# SDRAM.net
KiCad netlist of a schematic drawn in Altium Designer
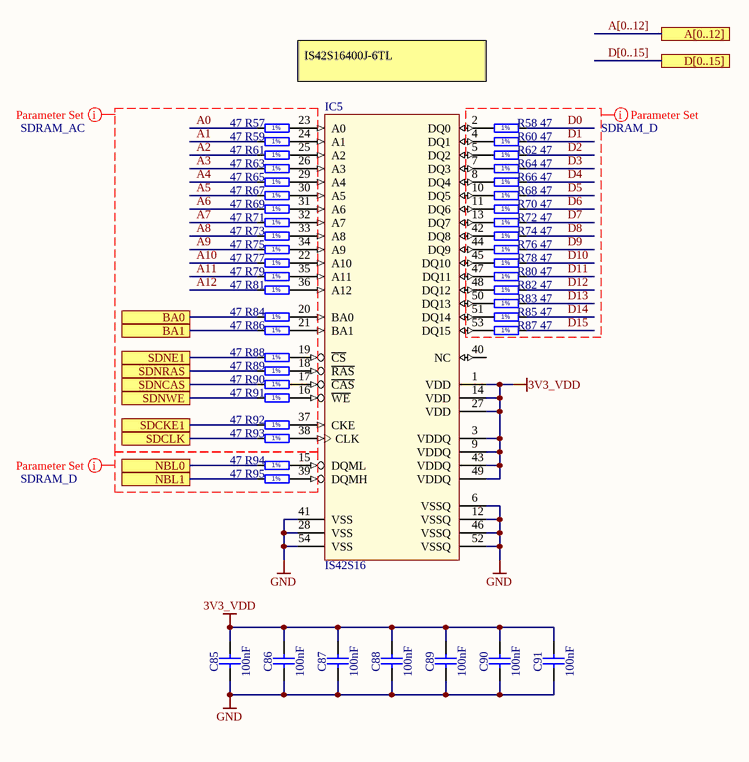
[diagram p0: SDRAM.SchDoc]

(export (version "E")
  (design (tool "Eeschema 10.0.6"))
  (components
    (comp (ref "C85")
      (value "100nF")
      (footprint "CAPC1005X55N")
      (description "Non-polarised capacitor")
      (fields
        (field (name "PART NUMBER") "CC0402_100NF_16V_10%_X5R")
        (field (name "VOLTAGE") "16V")
        (field (name "AUTHOR") "CERN DEM JLC")
      )
      (libsource (lib "Capacitors") (part "Capacitor - non polarized"))
    )
    (comp (ref "C86")
      (value "100nF")
      (footprint "CAPC1005X55N")
      (description "Non-polarised capacitor")
      (fields
        (field (name "PART NUMBER") "CC0402_100NF_16V_10%_X5R")
        (field (name "VOLTAGE") "16V")
        (field (name "AUTHOR") "CERN DEM JLC")
      )
      (libsource (lib "Capacitors") (part "Capacitor - non polarized"))
    )
    (comp (ref "C87")
      (value "100nF")
      (footprint "CAPC1005X55N")
      (description "Non-polarised capacitor")
      (fields
        (field (name "PART NUMBER") "CC0402_100NF_16V_10%_X5R")
        (field (name "VOLTAGE") "16V")
        (field (name "AUTHOR") "CERN DEM JLC")
      )
      (libsource (lib "Capacitors") (part "Capacitor - non polarized"))
    )
    (comp (ref "C88")
      (value "100nF")
      (footprint "CAPC1005X55N")
      (description "Non-polarised capacitor")
      (fields
        (field (name "PART NUMBER") "CC0402_100NF_16V_10%_X5R")
        (field (name "VOLTAGE") "16V")
        (field (name "AUTHOR") "CERN DEM JLC")
      )
      (libsource (lib "Capacitors") (part "Capacitor - non polarized"))
    )
    (comp (ref "C89")
      (value "100nF")
      (footprint "CAPC1005X55N")
      (description "Non-polarised capacitor")
      (fields
        (field (name "PART NUMBER") "CC0402_100NF_16V_10%_X5R")
        (field (name "VOLTAGE") "16V")
        (field (name "AUTHOR") "CERN DEM JLC")
      )
      (libsource (lib "Capacitors") (part "Capacitor - non polarized"))
    )
    (comp (ref "C90")
      (value "100nF")
      (footprint "CAPC1005X55N")
      (description "Non-polarised capacitor")
      (fields
        (field (name "PART NUMBER") "CC0402_100NF_16V_10%_X5R")
        (field (name "VOLTAGE") "16V")
        (field (name "AUTHOR") "CERN DEM JLC")
      )
      (libsource (lib "Capacitors") (part "Capacitor - non polarized"))
    )
    (comp (ref "C91")
      (value "100nF")
      (footprint "CAPC1005X55N")
      (description "Non-polarised capacitor")
      (fields
        (field (name "PART NUMBER") "CC0402_100NF_16V_10%_X5R")
        (field (name "VOLTAGE") "16V")
        (field (name "AUTHOR") "CERN DEM JLC")
      )
      (libsource (lib "Capacitors") (part "Capacitor - non polarized"))
    )
    (comp (ref "IC5")
      (value "IS42S16")
      (footprint "TSOP-54")
      (description "SDRAM 64m 200mhz 54tsop")
      (fields (field (name "MP") "IS42S16400J-5TL-TR") (field (name "MF") "ISSI"))
      (libsource (lib "IS42S16") (part "IS42S16"))
    )
    (comp (ref "R57")
      (value "47")
      (footprint "RESC1005X40N")
      (description "Resistor - 1%")
      (fields
        (field (name "PART NUMBER") "R0402_47R_1%_0.0625W_100PPM")
        (field (name "POWER") "0.0625W")
        (field (name "AUTHOR") "CERN DEM JLC")
      )
      (libsource (lib "Resistors") (part "Resistor - 1%"))
    )
    (comp (ref "R58")
      (value "47")
      (footprint "RESC1005X40N")
      (description "Resistor - 1%")
      (fields
        (field (name "PART NUMBER") "R0402_47R_1%_0.0625W_100PPM")
        (field (name "POWER") "0.0625W")
        (field (name "AUTHOR") "CERN DEM JLC")
      )
      (libsource (lib "Resistors") (part "Resistor - 1%"))
    )
    (comp (ref "R59")
      (value "47")
      (footprint "RESC1005X40N")
      (description "Resistor - 1%")
      (fields
        (field (name "PART NUMBER") "R0402_47R_1%_0.0625W_100PPM")
        (field (name "POWER") "0.0625W")
        (field (name "AUTHOR") "CERN DEM JLC")
      )
      (libsource (lib "Resistors") (part "Resistor - 1%"))
    )
    (comp (ref "R60")
      (value "47")
      (footprint "RESC1005X40N")
      (description "Resistor - 1%")
      (fields
        (field (name "PART NUMBER") "R0402_47R_1%_0.0625W_100PPM")
        (field (name "POWER") "0.0625W")
        (field (name "AUTHOR") "CERN DEM JLC")
      )
      (libsource (lib "Resistors") (part "Resistor - 1%"))
    )
    (comp (ref "R61")
      (value "47")
      (footprint "RESC1005X40N")
      (description "Resistor - 1%")
      (fields
        (field (name "PART NUMBER") "R0402_47R_1%_0.0625W_100PPM")
        (field (name "POWER") "0.0625W")
        (field (name "AUTHOR") "CERN DEM JLC")
      )
      (libsource (lib "Resistors") (part "Resistor - 1%"))
    )
    (comp (ref "R62")
      (value "47")
      (footprint "RESC1005X40N")
      (description "Resistor - 1%")
      (fields
        (field (name "PART NUMBER") "R0402_47R_1%_0.0625W_100PPM")
        (field (name "POWER") "0.0625W")
        (field (name "AUTHOR") "CERN DEM JLC")
      )
      (libsource (lib "Resistors") (part "Resistor - 1%"))
    )
    (comp (ref "R63")
      (value "47")
      (footprint "RESC1005X40N")
      (description "Resistor - 1%")
      (fields
        (field (name "PART NUMBER") "R0402_47R_1%_0.0625W_100PPM")
        (field (name "POWER") "0.0625W")
        (field (name "AUTHOR") "CERN DEM JLC")
      )
      (libsource (lib "Resistors") (part "Resistor - 1%"))
    )
    (comp (ref "R64")
      (value "47")
      (footprint "RESC1005X40N")
      (description "Resistor - 1%")
      (fields
        (field (name "PART NUMBER") "R0402_47R_1%_0.0625W_100PPM")
        (field (name "POWER") "0.0625W")
        (field (name "AUTHOR") "CERN DEM JLC")
      )
      (libsource (lib "Resistors") (part "Resistor - 1%"))
    )
    (comp (ref "R65")
      (value "47")
      (footprint "RESC1005X40N")
      (description "Resistor - 1%")
      (fields
        (field (name "PART NUMBER") "R0402_47R_1%_0.0625W_100PPM")
        (field (name "POWER") "0.0625W")
        (field (name "AUTHOR") "CERN DEM JLC")
      )
      (libsource (lib "Resistors") (part "Resistor - 1%"))
    )
    (comp (ref "R66")
      (value "47")
      (footprint "RESC1005X40N")
      (description "Resistor - 1%")
      (fields
        (field (name "PART NUMBER") "R0402_47R_1%_0.0625W_100PPM")
        (field (name "POWER") "0.0625W")
        (field (name "AUTHOR") "CERN DEM JLC")
      )
      (libsource (lib "Resistors") (part "Resistor - 1%"))
    )
    (comp (ref "R67")
      (value "47")
      (footprint "RESC1005X40N")
      (description "Resistor - 1%")
      (fields
        (field (name "PART NUMBER") "R0402_47R_1%_0.0625W_100PPM")
        (field (name "POWER") "0.0625W")
        (field (name "AUTHOR") "CERN DEM JLC")
      )
      (libsource (lib "Resistors") (part "Resistor - 1%"))
    )
    (comp (ref "R68")
      (value "47")
      (footprint "RESC1005X40N")
      (description "Resistor - 1%")
      (fields
        (field (name "PART NUMBER") "R0402_47R_1%_0.0625W_100PPM")
        (field (name "POWER") "0.0625W")
        (field (name "AUTHOR") "CERN DEM JLC")
      )
      (libsource (lib "Resistors") (part "Resistor - 1%"))
    )
    (comp (ref "R69")
      (value "47")
      (footprint "RESC1005X40N")
      (description "Resistor - 1%")
      (fields
        (field (name "PART NUMBER") "R0402_47R_1%_0.0625W_100PPM")
        (field (name "POWER") "0.0625W")
        (field (name "AUTHOR") "CERN DEM JLC")
      )
      (libsource (lib "Resistors") (part "Resistor - 1%"))
    )
    (comp (ref "R70")
      (value "47")
      (footprint "RESC1005X40N")
      (description "Resistor - 1%")
      (fields
        (field (name "PART NUMBER") "R0402_47R_1%_0.0625W_100PPM")
        (field (name "POWER") "0.0625W")
        (field (name "AUTHOR") "CERN DEM JLC")
      )
      (libsource (lib "Resistors") (part "Resistor - 1%"))
    )
    (comp (ref "R71")
      (value "47")
      (footprint "RESC1005X40N")
      (description "Resistor - 1%")
      (fields
        (field (name "PART NUMBER") "R0402_47R_1%_0.0625W_100PPM")
        (field (name "POWER") "0.0625W")
        (field (name "AUTHOR") "CERN DEM JLC")
      )
      (libsource (lib "Resistors") (part "Resistor - 1%"))
    )
    (comp (ref "R72")
      (value "47")
      (footprint "RESC1005X40N")
      (description "Resistor - 1%")
      (fields
        (field (name "PART NUMBER") "R0402_47R_1%_0.0625W_100PPM")
        (field (name "POWER") "0.0625W")
        (field (name "AUTHOR") "CERN DEM JLC")
      )
      (libsource (lib "Resistors") (part "Resistor - 1%"))
    )
    (comp (ref "R73")
      (value "47")
      (footprint "RESC1005X40N")
      (description "Resistor - 1%")
      (fields
        (field (name "PART NUMBER") "R0402_47R_1%_0.0625W_100PPM")
        (field (name "POWER") "0.0625W")
        (field (name "AUTHOR") "CERN DEM JLC")
      )
      (libsource (lib "Resistors") (part "Resistor - 1%"))
    )
    (comp (ref "R74")
      (value "47")
      (footprint "RESC1005X40N")
      (description "Resistor - 1%")
      (fields
        (field (name "PART NUMBER") "R0402_47R_1%_0.0625W_100PPM")
        (field (name "POWER") "0.0625W")
        (field (name "AUTHOR") "CERN DEM JLC")
      )
      (libsource (lib "Resistors") (part "Resistor - 1%"))
    )
    (comp (ref "R75")
      (value "47")
      (footprint "RESC1005X40N")
      (description "Resistor - 1%")
      (fields
        (field (name "PART NUMBER") "R0402_47R_1%_0.0625W_100PPM")
        (field (name "POWER") "0.0625W")
        (field (name "AUTHOR") "CERN DEM JLC")
      )
      (libsource (lib "Resistors") (part "Resistor - 1%"))
    )
    (comp (ref "R76")
      (value "47")
      (footprint "RESC1005X40N")
      (description "Resistor - 1%")
      (fields
        (field (name "PART NUMBER") "R0402_47R_1%_0.0625W_100PPM")
        (field (name "POWER") "0.0625W")
        (field (name "AUTHOR") "CERN DEM JLC")
      )
      (libsource (lib "Resistors") (part "Resistor - 1%"))
    )
    (comp (ref "R77")
      (value "47")
      (footprint "RESC1005X40N")
      (description "Resistor - 1%")
      (fields
        (field (name "PART NUMBER") "R0402_47R_1%_0.0625W_100PPM")
        (field (name "POWER") "0.0625W")
        (field (name "AUTHOR") "CERN DEM JLC")
      )
      (libsource (lib "Resistors") (part "Resistor - 1%"))
    )
    (comp (ref "R78")
      (value "47")
      (footprint "RESC1005X40N")
      (description "Resistor - 1%")
      (fields
        (field (name "PART NUMBER") "R0402_47R_1%_0.0625W_100PPM")
        (field (name "POWER") "0.0625W")
        (field (name "AUTHOR") "CERN DEM JLC")
      )
      (libsource (lib "Resistors") (part "Resistor - 1%"))
    )
    (comp (ref "R79")
      (value "47")
      (footprint "RESC1005X40N")
      (description "Resistor - 1%")
      (fields
        (field (name "PART NUMBER") "R0402_47R_1%_0.0625W_100PPM")
        (field (name "POWER") "0.0625W")
        (field (name "AUTHOR") "CERN DEM JLC")
      )
      (libsource (lib "Resistors") (part "Resistor - 1%"))
    )
    (comp (ref "R80")
      (value "47")
      (footprint "RESC1005X40N")
      (description "Resistor - 1%")
      (fields
        (field (name "PART NUMBER") "R0402_47R_1%_0.0625W_100PPM")
        (field (name "POWER") "0.0625W")
        (field (name "AUTHOR") "CERN DEM JLC")
      )
      (libsource (lib "Resistors") (part "Resistor - 1%"))
    )
    (comp (ref "R81")
      (value "47")
      (footprint "RESC1005X40N")
      (description "Resistor - 1%")
      (fields
        (field (name "PART NUMBER") "R0402_47R_1%_0.0625W_100PPM")
        (field (name "POWER") "0.0625W")
        (field (name "AUTHOR") "CERN DEM JLC")
      )
      (libsource (lib "Resistors") (part "Resistor - 1%"))
    )
    (comp (ref "R82")
      (value "47")
      (footprint "RESC1005X40N")
      (description "Resistor - 1%")
      (fields
        (field (name "PART NUMBER") "R0402_47R_1%_0.0625W_100PPM")
        (field (name "POWER") "0.0625W")
        (field (name "AUTHOR") "CERN DEM JLC")
      )
      (libsource (lib "Resistors") (part "Resistor - 1%"))
    )
    (comp (ref "R83")
      (value "47")
      (footprint "RESC1005X40N")
      (description "Resistor - 1%")
      (fields
        (field (name "PART NUMBER") "R0402_47R_1%_0.0625W_100PPM")
        (field (name "POWER") "0.0625W")
        (field (name "AUTHOR") "CERN DEM JLC")
      )
      (libsource (lib "Resistors") (part "Resistor - 1%"))
    )
    (comp (ref "R84")
      (value "47")
      (footprint "RESC1005X40N")
      (description "Resistor - 1%")
      (fields
        (field (name "PART NUMBER") "R0402_47R_1%_0.0625W_100PPM")
        (field (name "POWER") "0.0625W")
        (field (name "AUTHOR") "CERN DEM JLC")
      )
      (libsource (lib "Resistors") (part "Resistor - 1%"))
    )
    (comp (ref "R85")
      (value "47")
      (footprint "RESC1005X40N")
      (description "Resistor - 1%")
      (fields
        (field (name "PART NUMBER") "R0402_47R_1%_0.0625W_100PPM")
        (field (name "POWER") "0.0625W")
        (field (name "AUTHOR") "CERN DEM JLC")
      )
      (libsource (lib "Resistors") (part "Resistor - 1%"))
    )
    (comp (ref "R86")
      (value "47")
      (footprint "RESC1005X40N")
      (description "Resistor - 1%")
      (fields
        (field (name "PART NUMBER") "R0402_47R_1%_0.0625W_100PPM")
        (field (name "POWER") "0.0625W")
        (field (name "AUTHOR") "CERN DEM JLC")
      )
      (libsource (lib "Resistors") (part "Resistor - 1%"))
    )
    (comp (ref "R87")
      (value "47")
      (footprint "RESC1005X40N")
      (description "Resistor - 1%")
      (fields
        (field (name "PART NUMBER") "R0402_47R_1%_0.0625W_100PPM")
        (field (name "POWER") "0.0625W")
        (field (name "AUTHOR") "CERN DEM JLC")
      )
      (libsource (lib "Resistors") (part "Resistor - 1%"))
    )
    (comp (ref "R88")
      (value "47")
      (footprint "RESC1005X40N")
      (description "Resistor - 1%")
      (fields
        (field (name "PART NUMBER") "R0402_47R_1%_0.0625W_100PPM")
        (field (name "POWER") "0.0625W")
        (field (name "AUTHOR") "CERN DEM JLC")
      )
      (libsource (lib "Resistors") (part "Resistor - 1%"))
    )
    (comp (ref "R89")
      (value "47")
      (footprint "RESC1005X40N")
      (description "Resistor - 1%")
      (fields
        (field (name "PART NUMBER") "R0402_47R_1%_0.0625W_100PPM")
        (field (name "POWER") "0.0625W")
        (field (name "AUTHOR") "CERN DEM JLC")
      )
      (libsource (lib "Resistors") (part "Resistor - 1%"))
    )
    (comp (ref "R90")
      (value "47")
      (footprint "RESC1005X40N")
      (description "Resistor - 1%")
      (fields
        (field (name "PART NUMBER") "R0402_47R_1%_0.0625W_100PPM")
        (field (name "POWER") "0.0625W")
        (field (name "AUTHOR") "CERN DEM JLC")
      )
      (libsource (lib "Resistors") (part "Resistor - 1%"))
    )
    (comp (ref "R91")
      (value "47")
      (footprint "RESC1005X40N")
      (description "Resistor - 1%")
      (fields
        (field (name "PART NUMBER") "R0402_47R_1%_0.0625W_100PPM")
        (field (name "POWER") "0.0625W")
        (field (name "AUTHOR") "CERN DEM JLC")
      )
      (libsource (lib "Resistors") (part "Resistor - 1%"))
    )
    (comp (ref "R92")
      (value "47")
      (footprint "RESC1005X40N")
      (description "Resistor - 1%")
      (fields
        (field (name "PART NUMBER") "R0402_47R_1%_0.0625W_100PPM")
        (field (name "POWER") "0.0625W")
        (field (name "AUTHOR") "CERN DEM JLC")
      )
      (libsource (lib "Resistors") (part "Resistor - 1%"))
    )
    (comp (ref "R93")
      (value "47")
      (footprint "RESC1005X40N")
      (description "Resistor - 1%")
      (fields
        (field (name "PART NUMBER") "R0402_47R_1%_0.0625W_100PPM")
        (field (name "POWER") "0.0625W")
        (field (name "AUTHOR") "CERN DEM JLC")
      )
      (libsource (lib "Resistors") (part "Resistor - 1%"))
    )
    (comp (ref "R94")
      (value "47")
      (footprint "RESC1005X40N")
      (description "Resistor - 1%")
      (fields
        (field (name "PART NUMBER") "R0402_47R_1%_0.0625W_100PPM")
        (field (name "POWER") "0.0625W")
        (field (name "AUTHOR") "CERN DEM JLC")
      )
      (libsource (lib "Resistors") (part "Resistor - 1%"))
    )
    (comp (ref "R95")
      (value "47")
      (footprint "RESC1005X40N")
      (description "Resistor - 1%")
      (fields
        (field (name "PART NUMBER") "R0402_47R_1%_0.0625W_100PPM")
        (field (name "POWER") "0.0625W")
        (field (name "AUTHOR") "CERN DEM JLC")
      )
      (libsource (lib "Resistors") (part "Resistor - 1%"))
    )
  )
  (nets
    (net (code "1") (name "/A0") (class "Default")
      (node (ref "R57") (pin "2") (pinfunction "2_2") (pintype "passive"))
    )
    (net (code "2") (name "/A1") (class "Default")
      (node (ref "R59") (pin "2") (pinfunction "2_2") (pintype "passive"))
    )
    (net (code "3") (name "/A2") (class "Default")
      (node (ref "R61") (pin "2") (pinfunction "2_2") (pintype "passive"))
    )
    (net (code "4") (name "/A3") (class "Default")
      (node (ref "R63") (pin "2") (pinfunction "2_2") (pintype "passive"))
    )
    (net (code "5") (name "/A4") (class "Default")
      (node (ref "R65") (pin "2") (pinfunction "2_2") (pintype "passive"))
    )
    (net (code "6") (name "/A5") (class "Default")
      (node (ref "R67") (pin "2") (pinfunction "2_2") (pintype "passive"))
    )
    (net (code "7") (name "/A6") (class "Default")
      (node (ref "R69") (pin "2") (pinfunction "2_2") (pintype "passive"))
    )
    (net (code "8") (name "/A7") (class "Default")
      (node (ref "R71") (pin "2") (pinfunction "2_2") (pintype "passive"))
    )
    (net (code "9") (name "/A8") (class "Default")
      (node (ref "R73") (pin "2") (pinfunction "2_2") (pintype "passive"))
    )
    (net (code "10") (name "/A9") (class "Default")
      (node (ref "R75") (pin "2") (pinfunction "2_2") (pintype "passive"))
    )
    (net (code "11") (name "/A10") (class "Default")
      (node (ref "R77") (pin "2") (pinfunction "2_2") (pintype "passive"))
    )
    (net (code "12") (name "/A11") (class "Default")
      (node (ref "R79") (pin "2") (pinfunction "2_2") (pintype "passive"))
    )
    (net (code "13") (name "/A12") (class "Default")
      (node (ref "R81") (pin "2") (pinfunction "2_2") (pintype "passive"))
    )
    (net (code "15") (name "/BA0") (class "Default")
      (node (ref "R84") (pin "2") (pinfunction "2_2") (pintype "passive"))
    )
    (net (code "16") (name "/BA1") (class "Default")
      (node (ref "R86") (pin "2") (pinfunction "2_2") (pintype "passive"))
    )
    (net (code "17") (name "/D0") (class "Default")
      (node (ref "R58") (pin "2") (pinfunction "2_2") (pintype "passive"))
    )
    (net (code "18") (name "/D1") (class "Default")
      (node (ref "R60") (pin "2") (pinfunction "2_2") (pintype "passive"))
    )
    (net (code "19") (name "/D2") (class "Default")
      (node (ref "R62") (pin "2") (pinfunction "2_2") (pintype "passive"))
    )
    (net (code "20") (name "/D3") (class "Default")
      (node (ref "R64") (pin "2") (pinfunction "2_2") (pintype "passive"))
    )
    (net (code "21") (name "/D4") (class "Default")
      (node (ref "R66") (pin "2") (pinfunction "2_2") (pintype "passive"))
    )
    (net (code "22") (name "/D5") (class "Default")
      (node (ref "R68") (pin "2") (pinfunction "2_2") (pintype "passive"))
    )
    (net (code "23") (name "/D6") (class "Default")
      (node (ref "R70") (pin "2") (pinfunction "2_2") (pintype "passive"))
    )
    (net (code "24") (name "/D7") (class "Default")
      (node (ref "R72") (pin "2") (pinfunction "2_2") (pintype "passive"))
    )
    (net (code "25") (name "/D8") (class "Default")
      (node (ref "R74") (pin "2") (pinfunction "2_2") (pintype "passive"))
    )
    (net (code "26") (name "/D9") (class "Default")
      (node (ref "R76") (pin "2") (pinfunction "2_2") (pintype "passive"))
    )
    (net (code "27") (name "/D10") (class "Default")
      (node (ref "R78") (pin "2") (pinfunction "2_2") (pintype "passive"))
    )
    (net (code "28") (name "/D11") (class "Default")
      (node (ref "R80") (pin "2") (pinfunction "2_2") (pintype "passive"))
    )
    (net (code "29") (name "/D12") (class "Default")
      (node (ref "R82") (pin "2") (pinfunction "2_2") (pintype "passive"))
    )
    (net (code "30") (name "/D13") (class "Default")
      (node (ref "R83") (pin "2") (pinfunction "2_2") (pintype "passive"))
    )
    (net (code "31") (name "/D14") (class "Default")
      (node (ref "R85") (pin "2") (pinfunction "2_2") (pintype "passive"))
    )
    (net (code "32") (name "/D15") (class "Default")
      (node (ref "R87") (pin "2") (pinfunction "2_2") (pintype "passive"))
    )
    (net (code "34") (name "/NBL0") (class "Default")
      (node (ref "R94") (pin "2") (pinfunction "2_2") (pintype "passive"))
    )
    (net (code "35") (name "/NBL1") (class "Default")
      (node (ref "R95") (pin "2") (pinfunction "2_2") (pintype "passive"))
    )
    (net (code "36") (name "/SDCKE1") (class "Default")
      (node (ref "R92") (pin "2") (pinfunction "2_2") (pintype "passive"))
    )
    (net (code "37") (name "/SDCLK") (class "Default")
      (node (ref "R93") (pin "2") (pinfunction "2_2") (pintype "passive"))
    )
    (net (code "38") (name "/SDNCAS") (class "Default")
      (node (ref "R90") (pin "2") (pinfunction "2_2") (pintype "passive"))
    )
    (net (code "39") (name "/SDNE1") (class "Default")
      (node (ref "R88") (pin "2") (pinfunction "2_2") (pintype "passive"))
    )
    (net (code "40") (name "/SDNRAS") (class "Default")
      (node (ref "R89") (pin "2") (pinfunction "2_2") (pintype "passive"))
    )
    (net (code "41") (name "/SDNWE") (class "Default")
      (node (ref "R91") (pin "2") (pinfunction "2_2") (pintype "passive"))
    )
    (net (code "42") (name "3V3_VDD") (class "Default")
      (node (ref "C85") (pin "2") (pinfunction "2_2") (pintype "passive"))
      (node (ref "C86") (pin "2") (pinfunction "2_2") (pintype "passive"))
      (node (ref "C87") (pin "2") (pinfunction "2_2") (pintype "passive"))
      (node (ref "C88") (pin "2") (pinfunction "2_2") (pintype "passive"))
      (node (ref "C89") (pin "2") (pinfunction "2_2") (pintype "passive"))
      (node (ref "C90") (pin "2") (pinfunction "2_2") (pintype "passive"))
      (node (ref "C91") (pin "2") (pinfunction "2_2") (pintype "passive"))
      (node (ref "IC5") (pin "1") (pinfunction "VDD_1") (pintype "power_in"))
      (node (ref "IC5") (pin "14") (pinfunction "VDD_14") (pintype "power_in"))
      (node (ref "IC5") (pin "27") (pinfunction "VDD_27") (pintype "power_in"))
      (node (ref "IC5") (pin "3") (pinfunction "VDDQ_3") (pintype "power_in"))
      (node (ref "IC5") (pin "43") (pinfunction "VDDQ_43") (pintype "power_in"))
      (node (ref "IC5") (pin "49") (pinfunction "VDDQ_49") (pintype "power_in"))
      (node (ref "IC5") (pin "9") (pinfunction "VDDQ_9") (pintype "power_in"))
    )
    (net (code "43") (name "GND") (class "Default")
      (node (ref "C85") (pin "1") (pinfunction "1_1") (pintype "passive"))
      (node (ref "C86") (pin "1") (pinfunction "1_1") (pintype "passive"))
      (node (ref "C87") (pin "1") (pinfunction "1_1") (pintype "passive"))
      (node (ref "C88") (pin "1") (pinfunction "1_1") (pintype "passive"))
      (node (ref "C89") (pin "1") (pinfunction "1_1") (pintype "passive"))
      (node (ref "C90") (pin "1") (pinfunction "1_1") (pintype "passive"))
      (node (ref "C91") (pin "1") (pinfunction "1_1") (pintype "passive"))
      (node (ref "IC5") (pin "12") (pinfunction "VSSQ_12") (pintype "power_in"))
      (node (ref "IC5") (pin "28") (pinfunction "VSS_28") (pintype "power_in"))
      (node (ref "IC5") (pin "41") (pinfunction "VSS_41") (pintype "power_in"))
      (node (ref "IC5") (pin "46") (pinfunction "VSSQ_46") (pintype "power_in"))
      (node (ref "IC5") (pin "52") (pinfunction "VSSQ_52") (pintype "power_in"))
      (node (ref "IC5") (pin "54") (pinfunction "VSS_54") (pintype "power_in"))
      (node (ref "IC5") (pin "6") (pinfunction "VSSQ_6") (pintype "power_in"))
    )
    (net (code "44") (name "Net-(IC5-A0)") (class "Default")
      (node (ref "IC5") (pin "23") (pinfunction "A0_23") (pintype "input"))
      (node (ref "R57") (pin "1") (pinfunction "1_1") (pintype "passive"))
    )
    (net (code "45") (name "Net-(IC5-A1)") (class "Default")
      (node (ref "IC5") (pin "24") (pinfunction "A1_24") (pintype "input"))
      (node (ref "R59") (pin "1") (pinfunction "1_1") (pintype "passive"))
    )
    (net (code "46") (name "Net-(IC5-A2)") (class "Default")
      (node (ref "IC5") (pin "25") (pinfunction "A2_25") (pintype "input"))
      (node (ref "R61") (pin "1") (pinfunction "1_1") (pintype "passive"))
    )
    (net (code "47") (name "Net-(IC5-A3)") (class "Default")
      (node (ref "IC5") (pin "26") (pinfunction "A3_26") (pintype "input"))
      (node (ref "R63") (pin "1") (pinfunction "1_1") (pintype "passive"))
    )
    (net (code "48") (name "Net-(IC5-A4)") (class "Default")
      (node (ref "IC5") (pin "29") (pinfunction "A4_29") (pintype "input"))
      (node (ref "R65") (pin "1") (pinfunction "1_1") (pintype "passive"))
    )
    (net (code "49") (name "Net-(IC5-A5)") (class "Default")
      (node (ref "IC5") (pin "30") (pinfunction "A5_30") (pintype "input"))
      (node (ref "R67") (pin "1") (pinfunction "1_1") (pintype "passive"))
    )
    (net (code "50") (name "Net-(IC5-A6)") (class "Default")
      (node (ref "IC5") (pin "31") (pinfunction "A6_31") (pintype "input"))
      (node (ref "R69") (pin "1") (pinfunction "1_1") (pintype "passive"))
    )
    (net (code "51") (name "Net-(IC5-A7)") (class "Default")
      (node (ref "IC5") (pin "32") (pinfunction "A7_32") (pintype "input"))
      (node (ref "R71") (pin "1") (pinfunction "1_1") (pintype "passive"))
    )
    (net (code "52") (name "Net-(IC5-A8)") (class "Default")
      (node (ref "IC5") (pin "33") (pinfunction "A8_33") (pintype "input"))
      (node (ref "R73") (pin "1") (pinfunction "1_1") (pintype "passive"))
    )
    (net (code "53") (name "Net-(IC5-A9)") (class "Default")
      (node (ref "IC5") (pin "34") (pinfunction "A9_34") (pintype "input"))
      (node (ref "R75") (pin "1") (pinfunction "1_1") (pintype "passive"))
    )
    (net (code "54") (name "Net-(IC5-A10)") (class "Default")
      (node (ref "IC5") (pin "22") (pinfunction "A10_22") (pintype "input"))
      (node (ref "R77") (pin "1") (pinfunction "1_1") (pintype "passive"))
    )
    (net (code "55") (name "Net-(IC5-A11)") (class "Default")
      (node (ref "IC5") (pin "35") (pinfunction "A11_35") (pintype "input"))
      (node (ref "R79") (pin "1") (pinfunction "1_1") (pintype "passive"))
    )
    (net (code "56") (name "Net-(IC5-A12)") (class "Default")
      (node (ref "IC5") (pin "36") (pinfunction "A12_36") (pintype "input"))
      (node (ref "R81") (pin "1") (pinfunction "1_1") (pintype "passive"))
    )
    (net (code "57") (name "Net-(IC5-BA0)") (class "Default")
      (node (ref "IC5") (pin "20") (pinfunction "BA0_20") (pintype "input"))
      (node (ref "R84") (pin "1") (pinfunction "1_1") (pintype "passive"))
    )
    (net (code "58") (name "Net-(IC5-BA1)") (class "Default")
      (node (ref "IC5") (pin "21") (pinfunction "BA1_21") (pintype "input"))
      (node (ref "R86") (pin "1") (pinfunction "1_1") (pintype "passive"))
    )
    (net (code "59") (name "Net-(IC5-CKE)") (class "Default")
      (node (ref "IC5") (pin "37") (pinfunction "CKE_37") (pintype "input"))
      (node (ref "R92") (pin "1") (pinfunction "1_1") (pintype "passive"))
    )
    (net (code "60") (name "Net-(IC5-CLK)") (class "Default")
      (node (ref "IC5") (pin "38") (pinfunction "CLK_38") (pintype "input"))
      (node (ref "R93") (pin "1") (pinfunction "1_1") (pintype "passive"))
    )
    (net (code "61") (name "Net-(IC5-DQ0)") (class "Default")
      (node (ref "IC5") (pin "2") (pinfunction "DQ0_2") (pintype "bidirectional"))
      (node (ref "R58") (pin "1") (pinfunction "1_1") (pintype "passive"))
    )
    (net (code "62") (name "Net-(IC5-DQ1)") (class "Default")
      (node (ref "IC5") (pin "4") (pinfunction "DQ1_4") (pintype "bidirectional"))
      (node (ref "R60") (pin "1") (pinfunction "1_1") (pintype "passive"))
    )
    (net (code "63") (name "Net-(IC5-DQ2)") (class "Default")
      (node (ref "IC5") (pin "5") (pinfunction "DQ2_5") (pintype "bidirectional"))
      (node (ref "R62") (pin "1") (pinfunction "1_1") (pintype "passive"))
    )
    (net (code "64") (name "Net-(IC5-DQ3)") (class "Default")
      (node (ref "IC5") (pin "7") (pinfunction "DQ3_7") (pintype "bidirectional"))
      (node (ref "R64") (pin "1") (pinfunction "1_1") (pintype "passive"))
    )
    (net (code "65") (name "Net-(IC5-DQ4)") (class "Default")
      (node (ref "IC5") (pin "8") (pinfunction "DQ4_8") (pintype "bidirectional"))
      (node (ref "R66") (pin "1") (pinfunction "1_1") (pintype "passive"))
    )
    (net (code "66") (name "Net-(IC5-DQ5)") (class "Default")
      (node (ref "IC5") (pin "10") (pinfunction "DQ5_10") (pintype "bidirectional"))
      (node (ref "R68") (pin "1") (pinfunction "1_1") (pintype "passive"))
    )
    (net (code "67") (name "Net-(IC5-DQ6)") (class "Default")
      (node (ref "IC5") (pin "11") (pinfunction "DQ6_11") (pintype "bidirectional"))
      (node (ref "R70") (pin "1") (pinfunction "1_1") (pintype "passive"))
    )
    (net (code "68") (name "Net-(IC5-DQ7)") (class "Default")
      (node (ref "IC5") (pin "13") (pinfunction "DQ7_13") (pintype "bidirectional"))
      (node (ref "R72") (pin "1") (pinfunction "1_1") (pintype "passive"))
    )
    (net (code "69") (name "Net-(IC5-DQ8)") (class "Default")
      (node (ref "IC5") (pin "42") (pinfunction "DQ8_42") (pintype "bidirectional"))
      (node (ref "R74") (pin "1") (pinfunction "1_1") (pintype "passive"))
    )
    (net (code "70") (name "Net-(IC5-DQ9)") (class "Default")
      (node (ref "IC5") (pin "44") (pinfunction "DQ9_44") (pintype "bidirectional"))
      (node (ref "R76") (pin "1") (pinfunction "1_1") (pintype "passive"))
    )
    (net (code "71") (name "Net-(IC5-DQ10)") (class "Default")
      (node (ref "IC5") (pin "45") (pinfunction "DQ10_45") (pintype "bidirectional"))
      (node (ref "R78") (pin "1") (pinfunction "1_1") (pintype "passive"))
    )
    (net (code "72") (name "Net-(IC5-DQ11)") (class "Default")
      (node (ref "IC5") (pin "47") (pinfunction "DQ11_47") (pintype "bidirectional"))
      (node (ref "R80") (pin "1") (pinfunction "1_1") (pintype "passive"))
    )
    (net (code "73") (name "Net-(IC5-DQ12)") (class "Default")
      (node (ref "IC5") (pin "48") (pinfunction "DQ12_48") (pintype "bidirectional"))
      (node (ref "R82") (pin "1") (pinfunction "1_1") (pintype "passive"))
    )
    (net (code "74") (name "Net-(IC5-DQ13)") (class "Default")
      (node (ref "IC5") (pin "50") (pinfunction "DQ13_50") (pintype "bidirectional"))
      (node (ref "R83") (pin "1") (pinfunction "1_1") (pintype "passive"))
    )
    (net (code "75") (name "Net-(IC5-DQ14)") (class "Default")
      (node (ref "IC5") (pin "51") (pinfunction "DQ14_51") (pintype "bidirectional"))
      (node (ref "R85") (pin "1") (pinfunction "1_1") (pintype "passive"))
    )
    (net (code "76") (name "Net-(IC5-DQ15)") (class "Default")
      (node (ref "IC5") (pin "53") (pinfunction "DQ15_53") (pintype "bidirectional"))
      (node (ref "R87") (pin "1") (pinfunction "1_1") (pintype "passive"))
    )
    (net (code "77") (name "Net-(IC5-DQMH)") (class "Default")
      (node (ref "IC5") (pin "39") (pinfunction "DQMH_39") (pintype "input"))
      (node (ref "R95") (pin "1") (pinfunction "1_1") (pintype "passive"))
    )
    (net (code "78") (name "Net-(IC5-DQML)") (class "Default")
      (node (ref "IC5") (pin "15") (pinfunction "DQML_15") (pintype "input"))
      (node (ref "R94") (pin "1") (pinfunction "1_1") (pintype "passive"))
    )
    (net (code "79") (name "Net-(IC5-~{CAS})") (class "Default")
      (node (ref "IC5") (pin "17") (pinfunction "~{CAS}_17") (pintype "input"))
      (node (ref "R90") (pin "1") (pinfunction "1_1") (pintype "passive"))
    )
    (net (code "80") (name "Net-(IC5-~{CS})") (class "Default")
      (node (ref "IC5") (pin "19") (pinfunction "~{CS}_19") (pintype "input"))
      (node (ref "R88") (pin "1") (pinfunction "1_1") (pintype "passive"))
    )
    (net (code "81") (name "Net-(IC5-~{RAS})") (class "Default")
      (node (ref "IC5") (pin "18") (pinfunction "~{RAS}_18") (pintype "input"))
      (node (ref "R89") (pin "1") (pinfunction "1_1") (pintype "passive"))
    )
    (net (code "82") (name "Net-(IC5-~{WE})") (class "Default")
      (node (ref "IC5") (pin "16") (pinfunction "~{WE}_16") (pintype "input"))
      (node (ref "R91") (pin "1") (pinfunction "1_1") (pintype "passive"))
    )
    (net (code "83") (name "unconnected-(IC5-NC-Pad40)") (class "Default")
      (node (ref "IC5") (pin "40") (pinfunction "NC_40") (pintype "bidirectional"))
    )
  )
)
